# main_shema.net
KiCad netlist of a schematic drawn in EAGLE
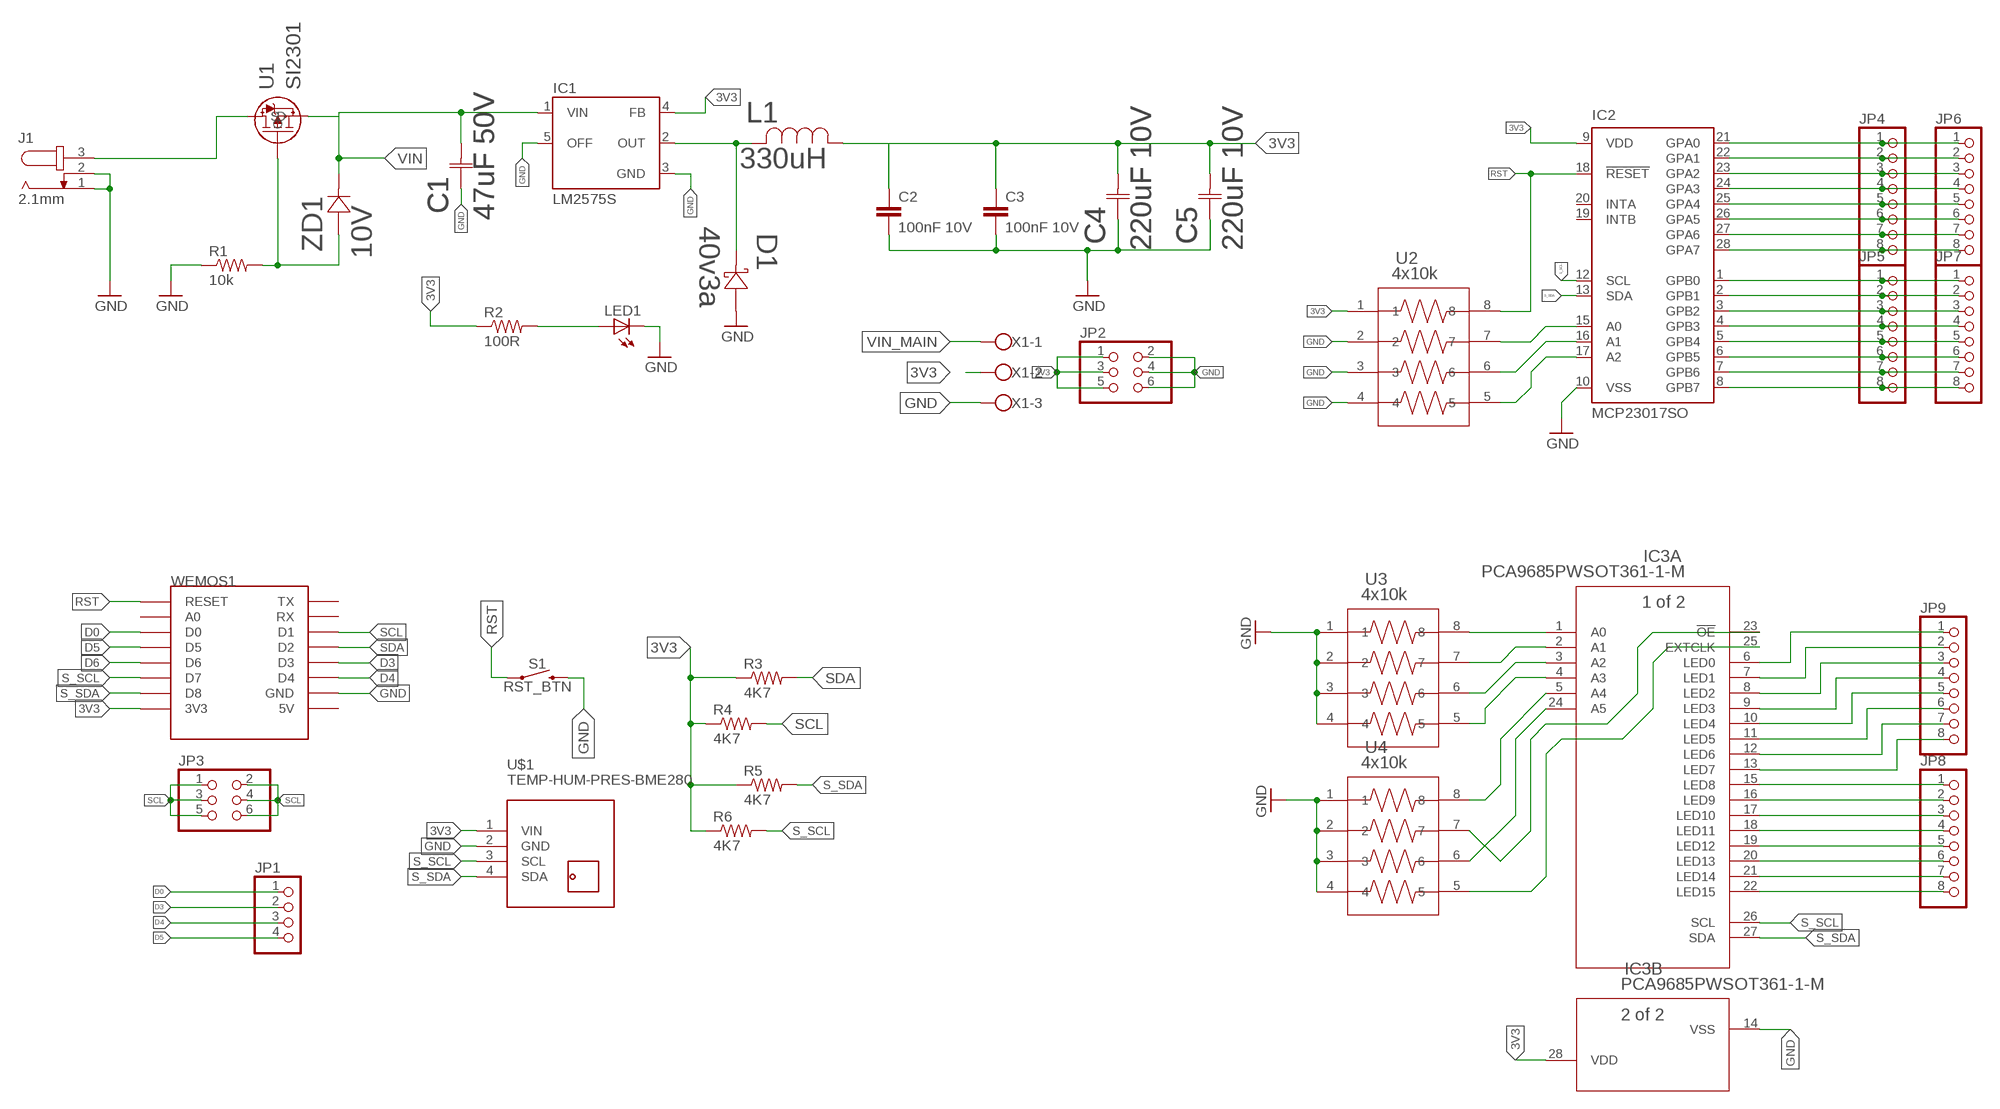
[diagram p0: schematic, sheet 1]

(export (version "E")
  (design (tool "Eeschema 10.0.6"))
  (components
    (comp (ref "C1")
      (value "47uF 50V")
      (footprint "eagle-import:CAP_EEE_D8-M")
      (fields (field (name "MANUFACTURER_PART_NUMBER") "EEE1HA470XP"))
      (libsource (lib "eagle-import") (part "EEE-1HA470XPCAP_EEE_D8-M"))
    )
    (comp (ref "C2")
      (value "100nF 10V")
      (footprint "eagle-import:C0603")
      (libsource (lib "eagle-import") (part "C-EUC0603"))
    )
    (comp (ref "C3")
      (value "100nF 10V")
      (footprint "eagle-import:C0603")
      (libsource (lib "eagle-import") (part "C-EUC0603"))
    )
    (comp (ref "C4")
      (value "220uF 10V")
      (footprint "eagle-import:CAP_EEE_D-M")
      (fields (field (name "MANUFACTURER_PART_NUMBER") "EEE0JA221WP"))
      (libsource (lib "eagle-import") (part "EEE-0JA221WPCAP_EEE_D-M"))
    )
    (comp (ref "C5")
      (value "220uF 10V")
      (footprint "eagle-import:CAP_EEE_D-M")
      (fields (field (name "MANUFACTURER_PART_NUMBER") "EEE0JA221WP"))
      (libsource (lib "eagle-import") (part "EEE-0JA221WPCAP_EEE_D-M"))
    )
    (comp (ref "D1")
      (value "40v3a")
      (footprint "eagle-import:CDBA-HF-M")
      (fields (field (name "MANUFACTURER_PART_NUMBER") "CDBA340HF"))
      (libsource (lib "eagle-import") (part "CDBA340-HFCDBA-HF-M"))
    )
    (comp (ref "IC1")
      (value "LM2575S")
      (footprint "eagle-import:TO263-5")
      (libsource (lib "eagle-import") (part "LM2575S"))
    )
    (comp (ref "IC2")
      (value "MCP23017SO")
      (footprint "eagle-import:SO28W")
      (fields (field (name "MF") "MICROCHIP") (field (name "MPN") "MCP23017-E/SO"))
      (libsource (lib "eagle-import") (part "MCP23017SO"))
    )
    (comp (ref "IC3")
      (value "PCA9685PWSOT361-1-M")
      (footprint "eagle-import:SOT361-1-M")
      (fields (field (name "MANUFACTURER_PART_NUMBER") "PCA9685PW"))
      (libsource (lib "eagle-import") (part "PCA9685PWSOT361-1-M"))
    )
    (comp (ref "J1")
      (value "2.1mm")
      (footprint "eagle-import:SPC4078")
      (libsource (lib "eagle-import") (part "JACK-PLUG1"))
    )
    (comp (ref "JP1")
      (value "PINHD-1X4")
      (footprint "eagle-import:1X04")
      (libsource (lib "eagle-import") (part "PINHD-1X4"))
    )
    (comp (ref "JP2")
      (value "PINHD-2X3")
      (footprint "eagle-import:2X03")
      (libsource (lib "eagle-import") (part "PINHD-2X3"))
    )
    (comp (ref "JP3")
      (value "PINHD-2X3")
      (footprint "eagle-import:2X03")
      (libsource (lib "eagle-import") (part "PINHD-2X3"))
    )
    (comp (ref "JP4")
      (value "PINHD-1X8")
      (footprint "eagle-import:1X08")
      (libsource (lib "eagle-import") (part "PINHD-1X8"))
    )
    (comp (ref "JP5")
      (value "PINHD-1X8")
      (footprint "eagle-import:1X08")
      (libsource (lib "eagle-import") (part "PINHD-1X8"))
    )
    (comp (ref "JP6")
      (value "PINHD-1X8")
      (footprint "eagle-import:1X08")
      (libsource (lib "eagle-import") (part "PINHD-1X8"))
    )
    (comp (ref "JP7")
      (value "PINHD-1X8")
      (footprint "eagle-import:1X08")
      (libsource (lib "eagle-import") (part "PINHD-1X8"))
    )
    (comp (ref "JP8")
      (value "PINHD-1X8/LONG")
      (footprint "eagle-import:1X08")
      (libsource (lib "eagle-import") (part "PINHD-1X8/LONG"))
    )
    (comp (ref "JP9")
      (value "PINHD-1X8/LONG")
      (footprint "eagle-import:1X08")
      (libsource (lib "eagle-import") (part "PINHD-1X8/LONG"))
    )
    (comp (ref "L1")
      (value "330uH")
      (footprint "eagle-import:IND_BOURNS_SRR1280")
      (fields (field (name "MANUFACTURER_PART_NUMBER") "SRR1280331K"))
      (libsource (lib "eagle-import") (part "SRR1280-331K"))
    )
    (comp (ref "LED1")
      (value "LED_E")
      (footprint "eagle-import:LED_1206")
      (libsource (lib "eagle-import") (part "LED_E"))
    )
    (comp (ref "R1")
      (value "10k")
      (footprint "eagle-import:R0603")
      (libsource (lib "eagle-import") (part "R-US_R0603"))
    )
    (comp (ref "R2")
      (value "100R")
      (footprint "eagle-import:R0603")
      (libsource (lib "eagle-import") (part "R-US_R0603"))
    )
    (comp (ref "R3")
      (value "4K7")
      (footprint "eagle-import:R0603")
      (libsource (lib "eagle-import") (part "R-US_R0603"))
    )
    (comp (ref "R4")
      (value "4K7")
      (footprint "eagle-import:R0603")
      (libsource (lib "eagle-import") (part "R-US_R0603"))
    )
    (comp (ref "R5")
      (value "4K7")
      (footprint "eagle-import:R0603")
      (libsource (lib "eagle-import") (part "R-US_R0603"))
    )
    (comp (ref "R6")
      (value "4K7")
      (footprint "eagle-import:R0603")
      (libsource (lib "eagle-import") (part "R-US_R0603"))
    )
    (comp (ref "S1")
      (value "RST_BTN")
      (footprint "eagle-import:TACTILE_SWITCH_PTH_6.0MM")
      (libsource (lib "eagle-import") (part "MOMENTARY-SWITCH-SPST-PTH-6.0MM"))
    )
    (comp (ref "U$1")
      (value "TEMP-HUM-PRES-BME280")
      (footprint "eagle-import:TEMP-HUM-PRES-BME280")
      (libsource (lib "eagle-import") (part "TEMP-HUM-PRES-BME280"))
    )
    (comp (ref "U1")
      (value "SI2301")
      (footprint "eagle-import:TO-236-M")
      (fields (field (name "MANUFACTURER_PART_NUMBER") "SI2301CDST1GE3"))
      (libsource (lib "eagle-import") (part "SI2301CDS-T1-GE3TO-236-M"))
    )
    (comp (ref "U2")
      (value "4x10k")
      (footprint "eagle-import:C_ARRAY_EXB38V")
      (fields (field (name "MANUFACTURER_PART_NUMBER") "EXB38V103JV"))
      (libsource (lib "eagle-import") (part "EXB-38V103JV"))
    )
    (comp (ref "U3")
      (value "4x10k")
      (footprint "eagle-import:C_ARRAY_EXB38V-M")
      (fields (field (name "MANUFACTURER_PART_NUMBER") "EXB38V103JV"))
      (libsource (lib "eagle-import") (part "EXB-38V103JVC_ARRAY_EXB38V-M"))
    )
    (comp (ref "U4")
      (value "4x10k")
      (footprint "eagle-import:C_ARRAY_EXB38V-M")
      (fields (field (name "MANUFACTURER_PART_NUMBER") "EXB38V103JV"))
      (libsource (lib "eagle-import") (part "EXB-38V103JVC_ARRAY_EXB38V-M"))
    )
    (comp (ref "WEMOS1")
      (value "WEMOS-D1-MINI")
      (footprint "eagle-import:WEMOS-D1-MINI")
      (libsource (lib "eagle-import") (part "WEMOS-D1-MINI"))
    )
    (comp (ref "X1")
      (value "W237-103")
      (footprint "eagle-import:W237-103")
      (fields (field (name "MPN") "237-103"))
      (libsource (lib "eagle-import") (part "W237-103"))
    )
    (comp (ref "ZD1")
      (value "10V")
      (footprint "eagle-import:SMINI2-F5-B-M")
      (fields (field (name "MANUFACTURER_PART_NUMBER") "DZ2J100M0L"))
      (libsource (lib "eagle-import") (part "DZ2J100M0LSMINI2-F5-B-M"))
    )
  )
  (nets
    (net (code "1") (name "3V3") (class "Default")
      (node (ref "C2") (pin "1") (pinfunction "1_1") (pintype "passive"))
      (node (ref "C3") (pin "1") (pinfunction "1_1") (pintype "passive"))
      (node (ref "C4") (pin "2") (pinfunction "22_2") (pintype "passive"))
      (node (ref "C5") (pin "2") (pinfunction "22_2") (pintype "passive"))
      (node (ref "IC1") (pin "4") (pinfunction "FB_4") (pintype "input"))
      (node (ref "IC2") (pin "9") (pinfunction "VDD_9") (pintype "power_in"))
      (node (ref "IC3") (pin "28") (pinfunction "VDD_28") (pintype "passive"))
      (node (ref "JP2") (pin "1") (pinfunction "1_1") (pintype "passive"))
      (node (ref "JP2") (pin "3") (pinfunction "3_3") (pintype "passive"))
      (node (ref "JP2") (pin "5") (pinfunction "5_5") (pintype "passive"))
      (node (ref "L1") (pin "1") (pinfunction "1_1") (pintype "passive"))
      (node (ref "R2") (pin "1") (pinfunction "1_1") (pintype "passive"))
      (node (ref "R3") (pin "1") (pinfunction "1_1") (pintype "passive"))
      (node (ref "R4") (pin "1") (pinfunction "1_1") (pintype "passive"))
      (node (ref "R5") (pin "1") (pinfunction "1_1") (pintype "passive"))
      (node (ref "R6") (pin "1") (pinfunction "1_1") (pintype "passive"))
      (node (ref "U$1") (pin "1") (pinfunction "VIN_1") (pintype "power_in"))
      (node (ref "U2") (pin "1") (pinfunction "1_1") (pintype "passive"))
      (node (ref "WEMOS1") (pin "3V3") (pinfunction "3V3_3V3") (pintype "bidirectional"))
      (node (ref "X1") (pin "2") (pinfunction "KL_2") (pintype "passive"))
    )
    (net (code "2") (name "D0") (class "Default")
      (node (ref "JP1") (pin "1") (pinfunction "1_1") (pintype "passive"))
      (node (ref "WEMOS1") (pin "D0") (pinfunction "D0_D0") (pintype "bidirectional"))
    )
    (net (code "3") (name "D3") (class "Default")
      (node (ref "JP1") (pin "2") (pinfunction "2_2") (pintype "passive"))
      (node (ref "WEMOS1") (pin "D3") (pinfunction "D3_D3") (pintype "bidirectional"))
    )
    (net (code "4") (name "D4") (class "Default")
      (node (ref "JP1") (pin "3") (pinfunction "3_3") (pintype "passive"))
      (node (ref "WEMOS1") (pin "D4") (pinfunction "D4_D4") (pintype "bidirectional"))
    )
    (net (code "5") (name "D5") (class "Default")
      (node (ref "JP1") (pin "4") (pinfunction "4_4") (pintype "passive"))
      (node (ref "WEMOS1") (pin "D5") (pinfunction "D5_D5") (pintype "bidirectional"))
    )
    (net (code "6") (name "D6") (class "Default")
      (node (ref "WEMOS1") (pin "D6") (pinfunction "D6_D6") (pintype "bidirectional"))
    )
    (net (code "7") (name "GND") (class "Default")
      (node (ref "C1") (pin "1") (pinfunction "11_1") (pintype "passive"))
      (node (ref "C2") (pin "2") (pinfunction "2_2") (pintype "passive"))
      (node (ref "C3") (pin "2") (pinfunction "2_2") (pintype "passive"))
      (node (ref "C4") (pin "1") (pinfunction "11_1") (pintype "passive"))
      (node (ref "C5") (pin "1") (pinfunction "11_1") (pintype "passive"))
      (node (ref "D1") (pin "2") (pinfunction "22_2") (pintype "passive"))
      (node (ref "IC1") (pin "3") (pinfunction "GND_3") (pintype "power_in"))
      (node (ref "IC1") (pin "5") (pinfunction "OFF_5") (pintype "input"))
      (node (ref "IC2") (pin "10") (pinfunction "VSS_10") (pintype "power_in"))
      (node (ref "IC3") (pin "14") (pinfunction "VSS_14") (pintype "passive"))
      (node (ref "J1") (pin "1") (pinfunction "1_1") (pintype "passive"))
      (node (ref "J1") (pin "2") (pinfunction "2_2") (pintype "passive"))
      (node (ref "JP2") (pin "2") (pinfunction "2_2") (pintype "passive"))
      (node (ref "JP2") (pin "4") (pinfunction "4_4") (pintype "passive"))
      (node (ref "JP2") (pin "6") (pinfunction "6_6") (pintype "passive"))
      (node (ref "LED1") (pin "C") (pinfunction "C_C") (pintype "passive"))
      (node (ref "R1") (pin "1") (pinfunction "1_1") (pintype "passive"))
      (node (ref "S1") (pin "3") (pinfunction "2_3") (pintype "passive"))
      (node (ref "U$1") (pin "2") (pinfunction "GND_2") (pintype "power_in"))
      (node (ref "U2") (pin "2") (pinfunction "2_2") (pintype "passive"))
      (node (ref "U2") (pin "3") (pinfunction "3_3") (pintype "passive"))
      (node (ref "U2") (pin "4") (pinfunction "4_4") (pintype "passive"))
      (node (ref "U3") (pin "1") (pinfunction "1_1") (pintype "passive"))
      (node (ref "U3") (pin "2") (pinfunction "2_2") (pintype "passive"))
      (node (ref "U3") (pin "3") (pinfunction "3_3") (pintype "passive"))
      (node (ref "U3") (pin "4") (pinfunction "4_4") (pintype "passive"))
      (node (ref "U4") (pin "1") (pinfunction "1_1") (pintype "passive"))
      (node (ref "U4") (pin "2") (pinfunction "2_2") (pintype "passive"))
      (node (ref "U4") (pin "3") (pinfunction "3_3") (pintype "passive"))
      (node (ref "U4") (pin "4") (pinfunction "4_4") (pintype "passive"))
      (node (ref "WEMOS1") (pin "GND") (pinfunction "GND_GND") (pintype "bidirectional"))
      (node (ref "X1") (pin "3") (pinfunction "KL_3") (pintype "passive"))
    )
    (net (code "8") (name "Net-(D1-11)") (class "Default")
      (node (ref "D1") (pin "1") (pinfunction "11_1") (pintype "passive"))
      (node (ref "IC1") (pin "2") (pinfunction "OUT_2") (pintype "output"))
      (node (ref "L1") (pin "2") (pinfunction "2_2") (pintype "passive"))
    )
    (net (code "9") (name "Net-(IC2-A0)") (class "Default")
      (node (ref "IC2") (pin "15") (pinfunction "A0_15") (pintype "input"))
      (node (ref "U2") (pin "7") (pinfunction "7_7") (pintype "passive"))
    )
    (net (code "10") (name "Net-(IC2-A1)") (class "Default")
      (node (ref "IC2") (pin "16") (pinfunction "A1_16") (pintype "input"))
      (node (ref "U2") (pin "6") (pinfunction "6_6") (pintype "passive"))
    )
    (net (code "11") (name "Net-(IC2-A2)") (class "Default")
      (node (ref "IC2") (pin "17") (pinfunction "A2_17") (pintype "input"))
      (node (ref "U2") (pin "5") (pinfunction "5_5") (pintype "passive"))
    )
    (net (code "12") (name "Net-(IC2-GPA0)") (class "Default")
      (node (ref "IC2") (pin "21") (pinfunction "GPA0_21") (pintype "bidirectional"))
      (node (ref "JP4") (pin "1") (pinfunction "1_1") (pintype "passive"))
      (node (ref "JP6") (pin "1") (pinfunction "1_1") (pintype "passive"))
    )
    (net (code "13") (name "Net-(IC2-GPA1)") (class "Default")
      (node (ref "IC2") (pin "22") (pinfunction "GPA1_22") (pintype "bidirectional"))
      (node (ref "JP4") (pin "2") (pinfunction "2_2") (pintype "passive"))
      (node (ref "JP6") (pin "2") (pinfunction "2_2") (pintype "passive"))
    )
    (net (code "14") (name "Net-(IC2-GPA2)") (class "Default")
      (node (ref "IC2") (pin "23") (pinfunction "GPA2_23") (pintype "bidirectional"))
      (node (ref "JP4") (pin "3") (pinfunction "3_3") (pintype "passive"))
      (node (ref "JP6") (pin "3") (pinfunction "3_3") (pintype "passive"))
    )
    (net (code "15") (name "Net-(IC2-GPA3)") (class "Default")
      (node (ref "IC2") (pin "24") (pinfunction "GPA3_24") (pintype "bidirectional"))
      (node (ref "JP4") (pin "4") (pinfunction "4_4") (pintype "passive"))
      (node (ref "JP6") (pin "4") (pinfunction "4_4") (pintype "passive"))
    )
    (net (code "16") (name "Net-(IC2-GPA4)") (class "Default")
      (node (ref "IC2") (pin "25") (pinfunction "GPA4_25") (pintype "bidirectional"))
      (node (ref "JP4") (pin "5") (pinfunction "5_5") (pintype "passive"))
      (node (ref "JP6") (pin "5") (pinfunction "5_5") (pintype "passive"))
    )
    (net (code "17") (name "Net-(IC2-GPA5)") (class "Default")
      (node (ref "IC2") (pin "26") (pinfunction "GPA5_26") (pintype "bidirectional"))
      (node (ref "JP4") (pin "6") (pinfunction "6_6") (pintype "passive"))
      (node (ref "JP6") (pin "6") (pinfunction "6_6") (pintype "passive"))
    )
    (net (code "18") (name "Net-(IC2-GPA6)") (class "Default")
      (node (ref "IC2") (pin "27") (pinfunction "GPA6_27") (pintype "bidirectional"))
      (node (ref "JP4") (pin "7") (pinfunction "7_7") (pintype "passive"))
      (node (ref "JP6") (pin "7") (pinfunction "7_7") (pintype "passive"))
    )
    (net (code "19") (name "Net-(IC2-GPA7)") (class "Default")
      (node (ref "IC2") (pin "28") (pinfunction "GPA7_28") (pintype "bidirectional"))
      (node (ref "JP4") (pin "8") (pinfunction "8_8") (pintype "passive"))
      (node (ref "JP6") (pin "8") (pinfunction "8_8") (pintype "passive"))
    )
    (net (code "20") (name "Net-(IC2-GPB0)") (class "Default")
      (node (ref "IC2") (pin "1") (pinfunction "GPB0_1") (pintype "bidirectional"))
      (node (ref "JP5") (pin "1") (pinfunction "1_1") (pintype "passive"))
      (node (ref "JP7") (pin "1") (pinfunction "1_1") (pintype "passive"))
    )
    (net (code "21") (name "Net-(IC2-GPB1)") (class "Default")
      (node (ref "IC2") (pin "2") (pinfunction "GPB1_2") (pintype "bidirectional"))
      (node (ref "JP5") (pin "2") (pinfunction "2_2") (pintype "passive"))
      (node (ref "JP7") (pin "2") (pinfunction "2_2") (pintype "passive"))
    )
    (net (code "22") (name "Net-(IC2-GPB2)") (class "Default")
      (node (ref "IC2") (pin "3") (pinfunction "GPB2_3") (pintype "bidirectional"))
      (node (ref "JP5") (pin "3") (pinfunction "3_3") (pintype "passive"))
      (node (ref "JP7") (pin "3") (pinfunction "3_3") (pintype "passive"))
    )
    (net (code "23") (name "Net-(IC2-GPB3)") (class "Default")
      (node (ref "IC2") (pin "4") (pinfunction "GPB3_4") (pintype "bidirectional"))
      (node (ref "JP5") (pin "4") (pinfunction "4_4") (pintype "passive"))
      (node (ref "JP7") (pin "4") (pinfunction "4_4") (pintype "passive"))
    )
    (net (code "24") (name "Net-(IC2-GPB4)") (class "Default")
      (node (ref "IC2") (pin "5") (pinfunction "GPB4_5") (pintype "bidirectional"))
      (node (ref "JP5") (pin "5") (pinfunction "5_5") (pintype "passive"))
      (node (ref "JP7") (pin "5") (pinfunction "5_5") (pintype "passive"))
    )
    (net (code "25") (name "Net-(IC2-GPB5)") (class "Default")
      (node (ref "IC2") (pin "6") (pinfunction "GPB5_6") (pintype "bidirectional"))
      (node (ref "JP5") (pin "6") (pinfunction "6_6") (pintype "passive"))
      (node (ref "JP7") (pin "6") (pinfunction "6_6") (pintype "passive"))
    )
    (net (code "26") (name "Net-(IC2-GPB6)") (class "Default")
      (node (ref "IC2") (pin "7") (pinfunction "GPB6_7") (pintype "bidirectional"))
      (node (ref "JP5") (pin "7") (pinfunction "7_7") (pintype "passive"))
      (node (ref "JP7") (pin "7") (pinfunction "7_7") (pintype "passive"))
    )
    (net (code "27") (name "Net-(IC2-GPB7)") (class "Default")
      (node (ref "IC2") (pin "8") (pinfunction "GPB7_8") (pintype "bidirectional"))
      (node (ref "JP5") (pin "8") (pinfunction "8_8") (pintype "passive"))
      (node (ref "JP7") (pin "8") (pinfunction "8_8") (pintype "passive"))
    )
    (net (code "28") (name "Net-(IC3A-A0)") (class "Default")
      (node (ref "IC3") (pin "1") (pinfunction "A0_1") (pintype "passive"))
      (node (ref "U3") (pin "8") (pinfunction "8_8") (pintype "passive"))
    )
    (net (code "29") (name "Net-(IC3A-A1)") (class "Default")
      (node (ref "IC3") (pin "2") (pinfunction "A1_2") (pintype "passive"))
      (node (ref "U3") (pin "7") (pinfunction "7_7") (pintype "passive"))
    )
    (net (code "30") (name "Net-(IC3A-A2)") (class "Default")
      (node (ref "IC3") (pin "3") (pinfunction "A2_3") (pintype "passive"))
      (node (ref "U3") (pin "6") (pinfunction "6_6") (pintype "passive"))
    )
    (net (code "31") (name "Net-(IC3A-A3)") (class "Default")
      (node (ref "IC3") (pin "4") (pinfunction "A3_4") (pintype "passive"))
      (node (ref "U3") (pin "5") (pinfunction "5_5") (pintype "passive"))
    )
    (net (code "32") (name "Net-(IC3A-A4)") (class "Default")
      (node (ref "IC3") (pin "5") (pinfunction "A4_5") (pintype "passive"))
      (node (ref "U4") (pin "8") (pinfunction "8_8") (pintype "passive"))
    )
    (net (code "33") (name "Net-(IC3A-A5)") (class "Default")
      (node (ref "IC3") (pin "24") (pinfunction "A5_24") (pintype "passive"))
      (node (ref "U4") (pin "6") (pinfunction "6_6") (pintype "passive"))
    )
    (net (code "34") (name "Net-(IC3A-EXTCLK)") (class "Default")
      (node (ref "IC3") (pin "25") (pinfunction "EXTCLK_25") (pintype "passive"))
      (node (ref "U4") (pin "5") (pinfunction "5_5") (pintype "passive"))
    )
    (net (code "35") (name "Net-(IC3A-LED0)") (class "Default")
      (node (ref "IC3") (pin "6") (pinfunction "LED0_6") (pintype "passive"))
      (node (ref "JP9") (pin "1") (pinfunction "1_1") (pintype "passive"))
    )
    (net (code "36") (name "Net-(IC3A-LED1)") (class "Default")
      (node (ref "IC3") (pin "7") (pinfunction "LED1_7") (pintype "passive"))
      (node (ref "JP9") (pin "2") (pinfunction "2_2") (pintype "passive"))
    )
    (net (code "37") (name "Net-(IC3A-LED2)") (class "Default")
      (node (ref "IC3") (pin "8") (pinfunction "LED2_8") (pintype "passive"))
      (node (ref "JP9") (pin "3") (pinfunction "3_3") (pintype "passive"))
    )
    (net (code "38") (name "Net-(IC3A-LED3)") (class "Default")
      (node (ref "IC3") (pin "9") (pinfunction "LED3_9") (pintype "passive"))
      (node (ref "JP9") (pin "4") (pinfunction "4_4") (pintype "passive"))
    )
    (net (code "39") (name "Net-(IC3A-LED4)") (class "Default")
      (node (ref "IC3") (pin "10") (pinfunction "LED4_10") (pintype "passive"))
      (node (ref "JP9") (pin "5") (pinfunction "5_5") (pintype "passive"))
    )
    (net (code "40") (name "Net-(IC3A-LED5)") (class "Default")
      (node (ref "IC3") (pin "11") (pinfunction "LED5_11") (pintype "passive"))
      (node (ref "JP9") (pin "6") (pinfunction "6_6") (pintype "passive"))
    )
    (net (code "41") (name "Net-(IC3A-LED6)") (class "Default")
      (node (ref "IC3") (pin "12") (pinfunction "LED6_12") (pintype "passive"))
      (node (ref "JP9") (pin "7") (pinfunction "7_7") (pintype "passive"))
    )
    (net (code "42") (name "Net-(IC3A-LED7)") (class "Default")
      (node (ref "IC3") (pin "13") (pinfunction "LED7_13") (pintype "passive"))
      (node (ref "JP9") (pin "8") (pinfunction "8_8") (pintype "passive"))
    )
    (net (code "43") (name "Net-(IC3A-LED8)") (class "Default")
      (node (ref "IC3") (pin "15") (pinfunction "LED8_15") (pintype "passive"))
      (node (ref "JP8") (pin "1") (pinfunction "1_1") (pintype "passive"))
    )
    (net (code "44") (name "Net-(IC3A-LED9)") (class "Default")
      (node (ref "IC3") (pin "16") (pinfunction "LED9_16") (pintype "passive"))
      (node (ref "JP8") (pin "2") (pinfunction "2_2") (pintype "passive"))
    )
    (net (code "45") (name "Net-(IC3A-LED10)") (class "Default")
      (node (ref "IC3") (pin "17") (pinfunction "LED10_17") (pintype "passive"))
      (node (ref "JP8") (pin "3") (pinfunction "3_3") (pintype "passive"))
    )
    (net (code "46") (name "Net-(IC3A-LED11)") (class "Default")
      (node (ref "IC3") (pin "18") (pinfunction "LED11_18") (pintype "passive"))
      (node (ref "JP8") (pin "4") (pinfunction "4_4") (pintype "passive"))
    )
    (net (code "47") (name "Net-(IC3A-LED12)") (class "Default")
      (node (ref "IC3") (pin "19") (pinfunction "LED12_19") (pintype "passive"))
      (node (ref "JP8") (pin "5") (pinfunction "5_5") (pintype "passive"))
    )
    (net (code "48") (name "Net-(IC3A-LED13)") (class "Default")
      (node (ref "IC3") (pin "20") (pinfunction "LED13_20") (pintype "passive"))
      (node (ref "JP8") (pin "6") (pinfunction "6_6") (pintype "passive"))
    )
    (net (code "49") (name "Net-(IC3A-LED14)") (class "Default")
      (node (ref "IC3") (pin "21") (pinfunction "LED14_21") (pintype "passive"))
      (node (ref "JP8") (pin "7") (pinfunction "7_7") (pintype "passive"))
    )
    (net (code "50") (name "Net-(IC3A-LED15)") (class "Default")
      (node (ref "IC3") (pin "22") (pinfunction "LED15_22") (pintype "passive"))
      (node (ref "JP8") (pin "8") (pinfunction "8_8") (pintype "passive"))
    )
    (net (code "51") (name "Net-(IC3A-~{OE})") (class "Default")
      (node (ref "IC3") (pin "23") (pinfunction "~{OE}_23") (pintype "passive"))
      (node (ref "U4") (pin "7") (pinfunction "7_7") (pintype "passive"))
    )
    (net (code "52") (name "Net-(LED1-PadA)") (class "Default")
      (node (ref "LED1") (pin "A") (pinfunction "A_A") (pintype "passive"))
      (node (ref "R2") (pin "2") (pinfunction "2_2") (pintype "passive"))
    )
    (net (code "53") (name "Net-(U1-G)") (class "Default")
      (node (ref "R1") (pin "2") (pinfunction "2_2") (pintype "passive"))
      (node (ref "U1") (pin "1") (pinfunction "G_1") (pintype "passive"))
      (node (ref "ZD1") (pin "2") (pinfunction "22_2") (pintype "passive"))
    )
    (net (code "54") (name "RST") (class "Default")
      (node (ref "IC2") (pin "18") (pinfunction "~{RESET}_18") (pintype "input"))
      (node (ref "S1") (pin "1") (pinfunction "1_1") (pintype "passive"))
      (node (ref "U2") (pin "8") (pinfunction "8_8") (pintype "passive"))
      (node (ref "WEMOS1") (pin "RESET") (pinfunction "RESET_RESET") (pintype "bidirectional"))
    )
    (net (code "55") (name "SCL") (class "Default")
      (node (ref "JP3") (pin "1") (pinfunction "1_1") (pintype "passive"))
      (node (ref "JP3") (pin "3") (pinfunction "3_3") (pintype "passive"))
      (node (ref "JP3") (pin "5") (pinfunction "5_5") (pintype "passive"))
      (node (ref "R4") (pin "2") (pinfunction "2_2") (pintype "passive"))
      (node (ref "WEMOS1") (pin "D1") (pinfunction "D1_D1") (pintype "bidirectional"))
    )
    (net (code "56") (name "SDA") (class "Default")
      (node (ref "JP3") (pin "2") (pinfunction "2_2") (pintype "passive"))
      (node (ref "JP3") (pin "4") (pinfunction "4_4") (pintype "passive"))
      (node (ref "JP3") (pin "6") (pinfunction "6_6") (pintype "passive"))
      (node (ref "R3") (pin "2") (pinfunction "2_2") (pintype "passive"))
      (node (ref "WEMOS1") (pin "D2") (pinfunction "D2_D2") (pintype "bidirectional"))
    )
    (net (code "57") (name "S_SCL") (class "Default")
      (node (ref "IC2") (pin "12") (pinfunction "SCL_12") (pintype "input"))
      (node (ref "IC3") (pin "26") (pinfunction "SCL_26") (pintype "passive"))
      (node (ref "R6") (pin "2") (pinfunction "2_2") (pintype "passive"))
      (node (ref "U$1") (pin "3") (pinfunction "SCL_3") (pintype "bidirectional"))
      (node (ref "WEMOS1") (pin "D7") (pinfunction "D7_D7") (pintype "bidirectional"))
    )
    (net (code "58") (name "S_SDA") (class "Default")
      (node (ref "IC2") (pin "13") (pinfunction "SDA_13") (pintype "bidirectional"))
      (node (ref "IC3") (pin "27") (pinfunction "SDA_27") (pintype "passive"))
      (node (ref "R5") (pin "2") (pinfunction "2_2") (pintype "passive"))
      (node (ref "U$1") (pin "4") (pinfunction "SDA_4") (pintype "bidirectional"))
      (node (ref "WEMOS1") (pin "D8") (pinfunction "D8_D8") (pintype "bidirectional"))
    )
    (net (code "59") (name "VIN") (class "Default")
      (node (ref "C1") (pin "2") (pinfunction "22_2") (pintype "passive"))
      (node (ref "IC1") (pin "1") (pinfunction "VIN_1") (pintype "power_in"))
      (node (ref "U1") (pin "2") (pinfunction "S_2") (pintype "passive"))
      (node (ref "ZD1") (pin "1") (pinfunction "11_1") (pintype "passive"))
    )
    (net (code "60") (name "VIN_MAIN") (class "Default")
      (node (ref "J1") (pin "3") (pinfunction "3_3") (pintype "passive"))
      (node (ref "U1") (pin "3") (pinfunction "D_3") (pintype "passive"))
      (node (ref "X1") (pin "1") (pinfunction "KL_1") (pintype "passive"))
    )
    (net (code "61") (name "unconnected-(IC2-INTA-Pad20)") (class "Default")
      (node (ref "IC2") (pin "20") (pinfunction "INTA_20") (pintype "output"))
    )
    (net (code "62") (name "unconnected-(IC2-INTB-Pad19)") (class "Default")
      (node (ref "IC2") (pin "19") (pinfunction "INTB_19") (pintype "output"))
    )
    (net (code "63") (name "unconnected-(WEMOS1-Pad5V)") (class "Default")
      (node (ref "WEMOS1") (pin "5V") (pinfunction "5V_5V") (pintype "bidirectional"))
    )
    (net (code "64") (name "unconnected-(WEMOS1-PadA0)") (class "Default")
      (node (ref "WEMOS1") (pin "A0") (pinfunction "A0_A0") (pintype "bidirectional"))
    )
    (net (code "65") (name "unconnected-(WEMOS1-PadRX)") (class "Default")
      (node (ref "WEMOS1") (pin "RX") (pinfunction "RX_RX") (pintype "bidirectional"))
    )
    (net (code "66") (name "unconnected-(WEMOS1-PadTX)") (class "Default")
      (node (ref "WEMOS1") (pin "TX") (pinfunction "TX_TX") (pintype "bidirectional"))
    )
  )
)
